# SCH_hackercard-3501_2024-09-02.net
KiCad netlist of a schematic drawn in EasyEDA
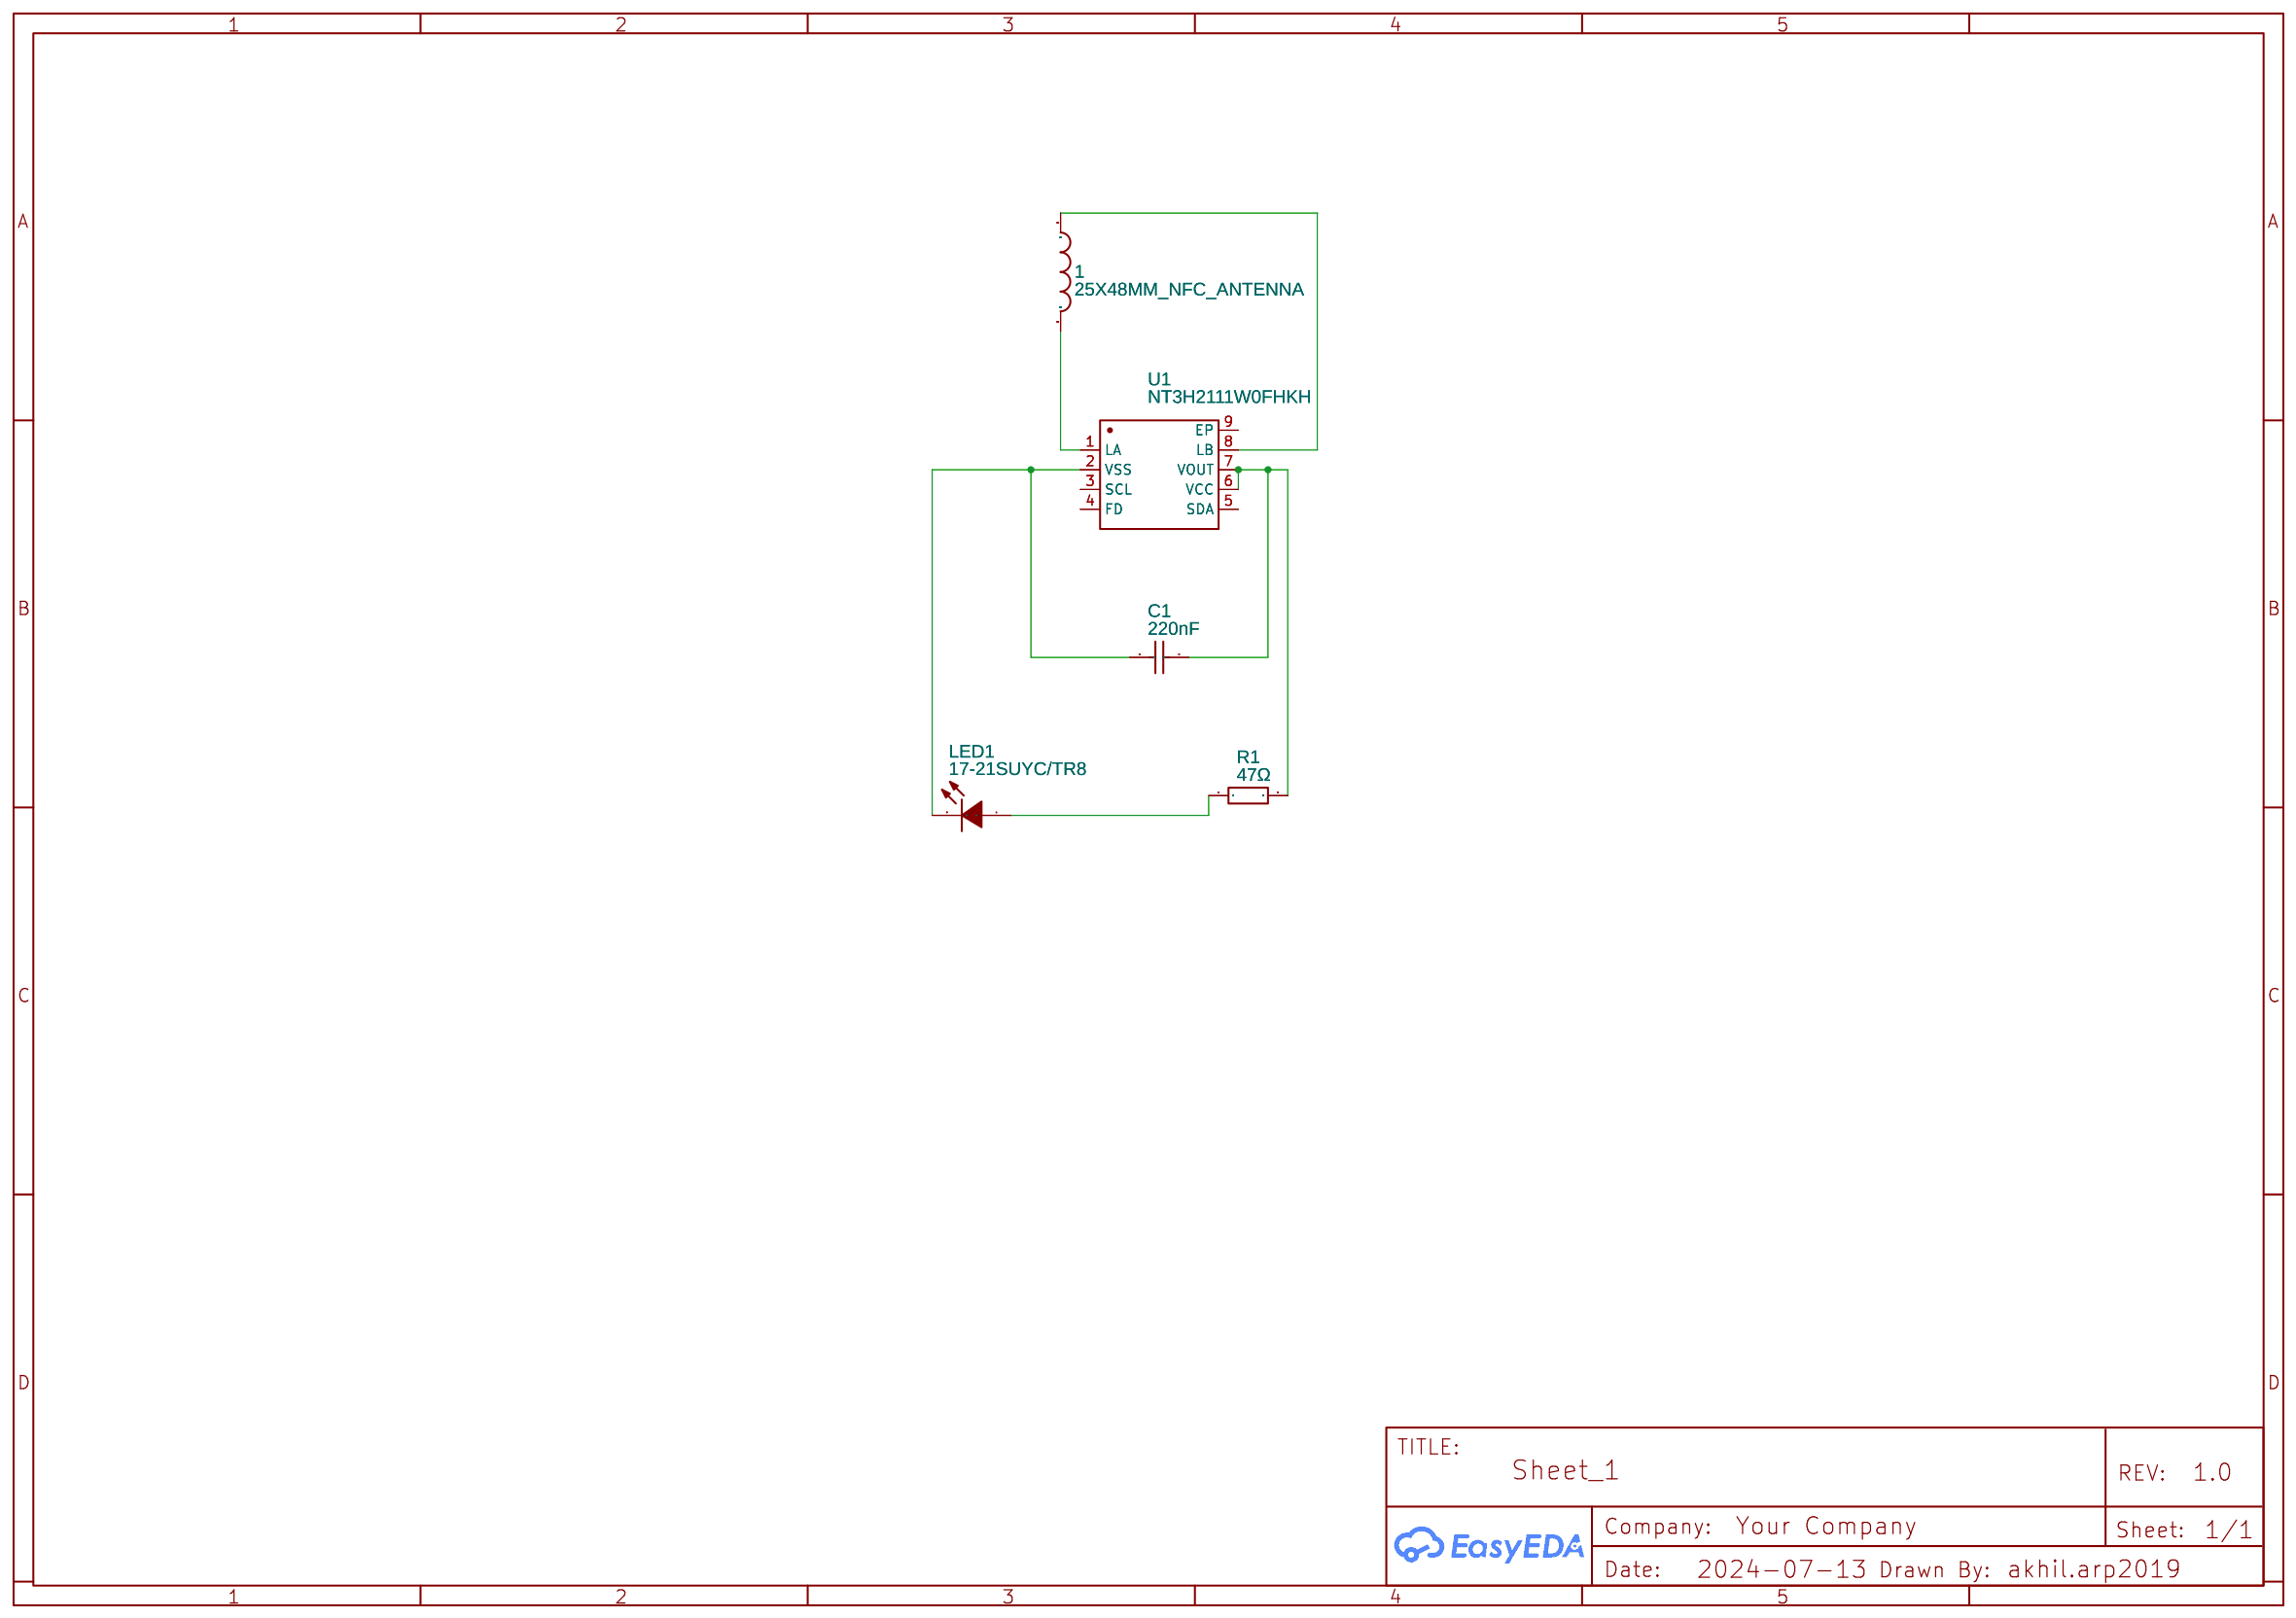
[diagram p0: schematic sheet]

(export (version "E")
  (design (tool "Eeschema 10.0.6"))
  (components
    (comp (ref "1") (value "25X48MM_NFC_ANTENNA") (libsource (lib "") (part "25X48MM_NFC_ANTENNA")))
    (comp (ref "C1")
      (value "220nF")
      (fields (field (name "Manufacturer Part") "C1005X5R0J224KT000F") (field (name "Manufacturer") "TDK"))
      (libsource (lib "") (part "C1005X5R0J224KT000F"))
    )
    (comp (ref "LED1")
      (value "17-21SUYC/TR8")
      (fields (field (name "Manufacturer Part") "KT-0805黄灯") (field (name "Manufacturer") "KENTO"))
      (libsource (lib "") (part "17-21SUYC/TR8"))
    )
    (comp (ref "R1")
      (value "47Ω")
      (fields
        (field (name "Manufacturer Part") "0603WAF470JT5E")
        (field (name "Manufacturer") "UNI-ROYAL(厚声)")
      )
      (libsource (lib "") (part "0603WAF470JT5E"))
    )
    (comp (ref "U1")
      (value "NT3H2111W0FHKH")
      (fields (field (name "Manufacturer") "NXP(恩智浦)"))
      (libsource (lib "") (part "NT3H2111W0FHKH"))
    )
  )
  (nets
    (net (code "1") (name "Net-(LED1-+)") (class "Default")
      (node (ref "LED1") (pin "1") (pinfunction "+_1") (pintype "unspecified"))
      (node (ref "R1") (pin "1") (pinfunction "1_1") (pintype "input"))
    )
    (net (code "2") (name "Net-(LED1--)") (class "Default")
      (node (ref "C1") (pin "1") (pinfunction "1_1") (pintype "input"))
      (node (ref "LED1") (pin "2") (pinfunction "-_2") (pintype "unspecified"))
      (node (ref "U1") (pin "2") (pinfunction "VSS_2") (pintype "unspecified"))
    )
    (net (code "3") (name "Net-(U1-LA)") (class "Default")
      (node (ref "1") (pin "P$2") (pinfunction "P$2_P$2") (pintype "bidirectional"))
      (node (ref "U1") (pin "1") (pinfunction "LA_1") (pintype "unspecified"))
    )
    (net (code "4") (name "Net-(U1-LB)") (class "Default")
      (node (ref "1") (pin "P$1") (pinfunction "P$1_P$1") (pintype "bidirectional"))
      (node (ref "U1") (pin "8") (pinfunction "LB_8") (pintype "unspecified"))
    )
    (net (code "5") (name "Net-(U1-VCC)") (class "Default")
      (node (ref "C1") (pin "2") (pinfunction "2_2") (pintype "input"))
      (node (ref "R1") (pin "2") (pinfunction "2_2") (pintype "input"))
      (node (ref "U1") (pin "6") (pinfunction "VCC_6") (pintype "unspecified"))
      (node (ref "U1") (pin "7") (pinfunction "VOUT_7") (pintype "unspecified"))
    )
    (net (code "6") (name "unconnected-(U1-EP-Pad9)") (class "Default")
      (node (ref "U1") (pin "9") (pinfunction "EP_9") (pintype "unspecified"))
    )
    (net (code "7") (name "unconnected-(U1-FD-Pad4)") (class "Default")
      (node (ref "U1") (pin "4") (pinfunction "FD_4") (pintype "unspecified"))
    )
    (net (code "8") (name "unconnected-(U1-SCL-Pad3)") (class "Default")
      (node (ref "U1") (pin "3") (pinfunction "SCL_3") (pintype "unspecified"))
    )
    (net (code "9") (name "unconnected-(U1-SDA-Pad5)") (class "Default")
      (node (ref "U1") (pin "5") (pinfunction "SDA_5") (pintype "unspecified"))
    )
  )
)
